# Input.net
KiCad netlist of a schematic drawn in Altium Designer
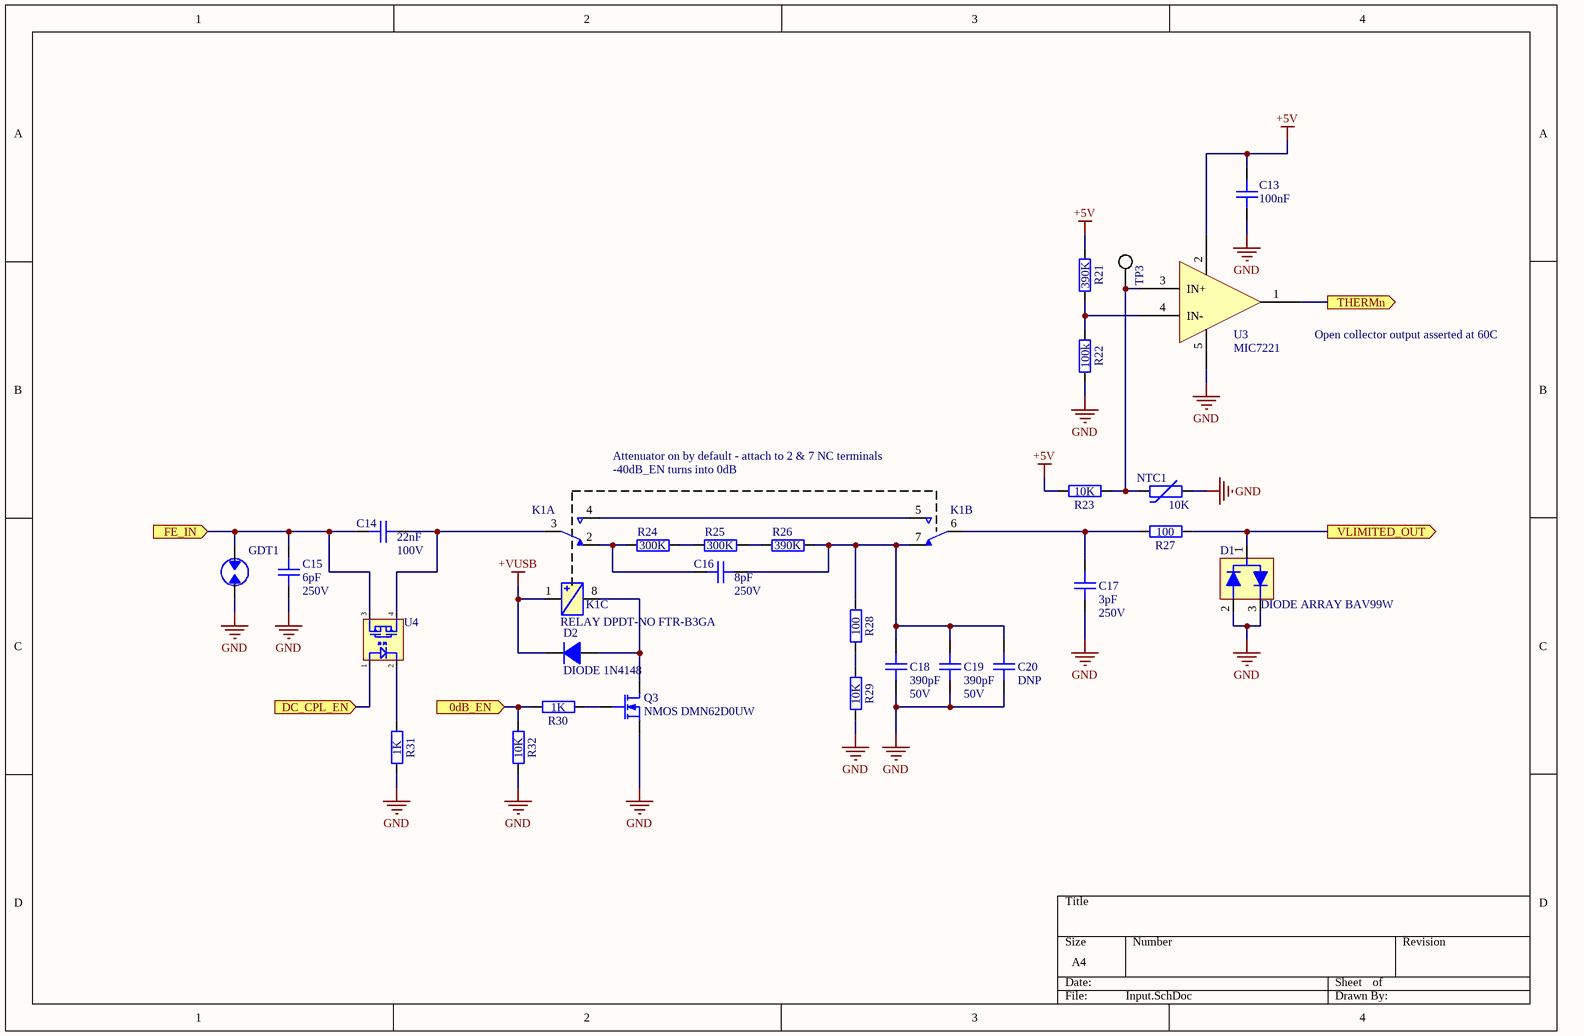
[diagram p0: Input.SchDoc]

(export (version "E")
  (design (tool "Eeschema 10.0.6"))
  (components
    (comp (ref "C13")
      (value "100nF")
      (footprint "GEN_C_0402")
      (fields (field (name "Comment") "CAP 100nF 16V X7R 0402"))
      (libsource (lib "DSO") (part "CAP 100nF 16V X7R 0402"))
    )
    (comp (ref "C14")
      (value "22nF")
      (footprint "GEN_C_0603")
      (fields (field (name "VOLTAGE RATING") "100V") (field (name "Comment") "CAP 22nF 100V X7R 0603"))
      (libsource (lib "DSO") (part "CAP 22nF 100V X7R 0603"))
    )
    (comp (ref "C15")
      (value "6pF")
      (footprint "GEN_C_0603")
      (fields (field (name "VOLTAGE RATING") "250V") (field (name "Comment") "CAP 6pF 250V C0G 0603"))
      (libsource (lib "DSO") (part "CAP 6pF 250V C0G 0603"))
    )
    (comp (ref "C16")
      (value "8pF")
      (footprint "GEN_C_0603")
      (fields (field (name "VOLTAGE RATING") "250V") (field (name "Comment") "CAP 8pF 250V C0G 0603"))
      (libsource (lib "DSO") (part "CAP 8pF 250V C0G 0603"))
    )
    (comp (ref "C17")
      (value "3pF")
      (footprint "GEN_C_0603")
      (fields (field (name "VOLTAGE RATING") "250V") (field (name "Comment") "CAP 3pF 250V C0G 0603"))
      (libsource (lib "DSO") (part "CAP 3pF 250V C0G 0603"))
    )
    (comp (ref "C18")
      (value "390pF")
      (footprint "GEN_C_0402")
      (fields (field (name "VOLTAGE RATING") "50V") (field (name "Comment") "CAP 390pF 50V C0G 0402"))
      (libsource (lib "DSO") (part "CAP 390pF 50V C0G 0402"))
    )
    (comp (ref "C19")
      (value "390pF")
      (footprint "GEN_C_0402")
      (fields (field (name "VOLTAGE RATING") "50V") (field (name "Comment") "CAP 390pF 50V C0G 0402"))
      (libsource (lib "DSO") (part "CAP 390pF 50V C0G 0402"))
    )
    (comp (ref "C20")
      (value "DNP")
      (footprint "GEN_C_0402")
      (fields (field (name "Comment") "CAP DNP 0402"))
      (libsource (lib "DSO") (part "CAP DNP 0402"))
    )
    (comp (ref "D1")
      (value "DIODE ARRAY BAV99W")
      (footprint "GEN_SOT_323")
      (libsource (lib "DSO") (part "DIODE ARRAY BAV99W"))
    )
    (comp (ref "D2")
      (value "DIODE 1N4148")
      (footprint "GEN_SOD_323")
      (libsource (lib "DSO") (part "DIODE 1N4148"))
    )
    (comp (ref "GDT1") (value "GDT 90V") (footprint "BOU_2051") (libsource (lib "DSO") (part "GDT 90V")))
    (comp (ref "K1")
      (value "RELAY DPDT-NO FTR-B3GA")
      (footprint "FUJ_FTR-B3GA")
      (libsource (lib "") (part "RELAY DPDT-NO FTR-B3GA_1"))
    )
    (comp (ref "NTC1")
      (value "10K")
      (footprint "GEN_R_0402")
      (fields (field (name "Comment") "NTC 10K 3900K 0402"))
      (libsource (lib "DSO") (part "NTC 10K 3900K 0402"))
    )
    (comp (ref "Q3")
      (value "NMOS DMN62D0UW")
      (footprint "GEN_SOT_323")
      (libsource (lib "DSO") (part "NMOS DMN62D0UW"))
    )
    (comp (ref "R21")
      (value "390K")
      (footprint "GEN_R_0402")
      (fields (field (name "TOLERANCE") "1%") (field (name "Comment") "RES 390K OHM 1% 1/10W 0402"))
      (libsource (lib "") (part "RES 390K OHM 1% 1/10W 0402_1"))
    )
    (comp (ref "R22")
      (value "100k")
      (footprint "GEN_R_0402")
      (fields (field (name "TOLERANCE") "1%") (field (name "Comment") "RES 100K OHM 1% 1/10W 0402"))
      (libsource (lib "DSO") (part "RES 100K OHM 1% 1/10W 0402"))
    )
    (comp (ref "R23")
      (value "10K")
      (footprint "GEN_R_0402")
      (fields (field (name "TOLERANCE") "1%") (field (name "Comment") "RES 10K OHM 1% 1/10W 0402"))
      (libsource (lib "") (part "RES 10K OHM 1% 1/10W 0402_1"))
    )
    (comp (ref "R24")
      (value "300K")
      (footprint "GEN_R_0402")
      (fields (field (name "TOLERANCE") "1%") (field (name "Comment") "RES 300K OHM 1% 1/10W 0402"))
      (libsource (lib "DSO") (part "RES 300K OHM 1% 1/10W 0402"))
    )
    (comp (ref "R25")
      (value "300K")
      (footprint "GEN_R_0402")
      (fields (field (name "TOLERANCE") "1%") (field (name "Comment") "RES 300K OHM 1% 1/10W 0402"))
      (libsource (lib "DSO") (part "RES 300K OHM 1% 1/10W 0402"))
    )
    (comp (ref "R26")
      (value "390K")
      (footprint "GEN_R_0402")
      (fields (field (name "TOLERANCE") "1%") (field (name "Comment") "RES 390K OHM 1% 1/10W 0402"))
      (libsource (lib "DSO") (part "RES 390K OHM 1% 1/10W 0402"))
    )
    (comp (ref "R27")
      (value "100")
      (footprint "GEN_R_0402")
      (fields (field (name "TOLERANCE") "1%") (field (name "Comment") "RES 100 OHM 1% 1/10W 0402"))
      (libsource (lib "DSO") (part "RES 100 OHM 1% 1/10W 0402"))
    )
    (comp (ref "R28")
      (value "100")
      (footprint "GEN_R_0402")
      (fields (field (name "TOLERANCE") "1%") (field (name "Comment") "RES 100 OHM 1% 1/10W 0402"))
      (libsource (lib "") (part "RES 100 OHM 1% 1/10W 0402_1"))
    )
    (comp (ref "R29")
      (value "10K")
      (footprint "GEN_R_0402")
      (fields (field (name "TOLERANCE") "1%") (field (name "Comment") "RES 10K OHM 1% 1/10W 0402"))
      (libsource (lib "DSO") (part "RES 10K OHM 1% 1/10W 0402"))
    )
    (comp (ref "R30")
      (value "1K")
      (footprint "GEN_R_0402")
      (fields (field (name "TOLERANCE") "1%") (field (name "Comment") "RES 1K OHM 1% 1/10W 0402"))
      (libsource (lib "") (part "RES 1K OHM 1% 1/10W 0402_1"))
    )
    (comp (ref "R31")
      (value "1K")
      (footprint "GEN_R_0402")
      (fields (field (name "TOLERANCE") "1%") (field (name "Comment") "RES 1K OHM 1% 1/10W 0402"))
      (libsource (lib "DSO") (part "RES 1K OHM 1% 1/10W 0402"))
    )
    (comp (ref "R32")
      (value "10K")
      (footprint "GEN_R_0402")
      (fields (field (name "TOLERANCE") "1%") (field (name "Comment") "RES 10K OHM 1% 1/10W 0402"))
      (libsource (lib "DSO") (part "RES 10K OHM 1% 1/10W 0402"))
    )
    (comp (ref "TP3") (value "5019") (footprint "KEY_5019") (libsource (lib "DSO") (part "TP KEYSTONE 5019")))
    (comp (ref "U3")
      (value "MIC7221")
      (footprint "GEN_SOT23_5_950_2900X1600X1450")
      (libsource (lib "DSO") (part "IC COMP MIC7221YM5"))
    )
    (comp (ref "U4")
      (value "SSR CPC1017NTR")
      (footprint "IXY_CPC1017")
      (libsource (lib "DSO") (part "SSR CPC1017NTR"))
    )
  )
  (nets
    (net (code "1") (name "+5V") (class "Default")
      (node (ref "C13") (pin "1") (pinfunction "1_1") (pintype "passive"))
      (node (ref "R21") (pin "1") (pinfunction "1_1") (pintype "passive"))
      (node (ref "R23") (pin "2") (pinfunction "2_2") (pintype "passive"))
      (node (ref "U3") (pin "2") (pinfunction "V+_2") (pintype "passive"))
    )
    (net (code "2") (name "+VUSB") (class "Default")
      (node (ref "D2") (pin "1") (pinfunction "K_1") (pintype "passive"))
      (node (ref "K1") (pin "1") (pinfunction "1_1") (pintype "passive"))
    )
    (net (code "3") (name "/0dB_EN") (class "Default")
      (node (ref "R30") (pin "2") (pinfunction "2_2") (pintype "passive"))
      (node (ref "R32") (pin "2") (pinfunction "2_2") (pintype "passive"))
    )
    (net (code "4") (name "/DC_CPL_EN") (class "Default")
      (node (ref "U4") (pin "1") (pinfunction "1_1") (pintype "passive"))
    )
    (net (code "5") (name "/FE_IN") (class "Default")
      (node (ref "C14") (pin "2") (pinfunction "2_2") (pintype "passive"))
      (node (ref "C15") (pin "2") (pinfunction "2_2") (pintype "passive"))
      (node (ref "GDT1") (pin "1") (pinfunction "1_1") (pintype "passive"))
      (node (ref "U4") (pin "3") (pinfunction "3_3") (pintype "passive"))
    )
    (net (code "6") (name "/THERMn") (class "Default")
      (node (ref "U3") (pin "1") (pinfunction "OUT_1") (pintype "open_collector"))
    )
    (net (code "7") (name "/VLIMITED_OUT") (class "Default")
      (node (ref "D1") (pin "1") (pintype "passive"))
      (node (ref "R27") (pin "1") (pinfunction "1_1") (pintype "passive"))
    )
    (net (code "8") (name "GND") (class "Default")
      (node (ref "C13") (pin "2") (pinfunction "2_2") (pintype "passive"))
      (node (ref "C15") (pin "1") (pinfunction "1_1") (pintype "passive"))
      (node (ref "C17") (pin "2") (pinfunction "2_2") (pintype "passive"))
      (node (ref "C18") (pin "1") (pinfunction "1_1") (pintype "passive"))
      (node (ref "C19") (pin "1") (pinfunction "1_1") (pintype "passive"))
      (node (ref "C20") (pin "1") (pinfunction "1_1") (pintype "passive"))
      (node (ref "D1") (pin "2") (pinfunction "2_2") (pintype "passive"))
      (node (ref "D1") (pin "3") (pinfunction "3_3") (pintype "passive"))
      (node (ref "GDT1") (pin "2") (pinfunction "2_2") (pintype "passive"))
      (node (ref "NTC1") (pin "2") (pinfunction "2_2") (pintype "passive"))
      (node (ref "Q3") (pin "3") (pinfunction "S_3") (pintype "passive"))
      (node (ref "R22") (pin "2") (pinfunction "2_2") (pintype "passive"))
      (node (ref "R29") (pin "1") (pinfunction "1_1") (pintype "passive"))
      (node (ref "R31") (pin "1") (pinfunction "1_1") (pintype "passive"))
      (node (ref "R32") (pin "1") (pinfunction "1_1") (pintype "passive"))
      (node (ref "U3") (pin "5") (pinfunction "V-_5") (pintype "passive"))
    )
    (net (code "9") (name "Net-(C14-Pad1)") (class "Default")
      (node (ref "C14") (pin "1") (pinfunction "1_1") (pintype "passive"))
      (node (ref "K1") (pin "3") (pinfunction "3_3") (pintype "passive"))
      (node (ref "U4") (pin "4") (pinfunction "4_4") (pintype "passive"))
    )
    (net (code "10") (name "Net-(C16-Pad1)") (class "Default")
      (node (ref "C16") (pin "1") (pinfunction "1_1") (pintype "passive"))
      (node (ref "C18") (pin "2") (pinfunction "2_2") (pintype "passive"))
      (node (ref "C19") (pin "2") (pinfunction "2_2") (pintype "passive"))
      (node (ref "C20") (pin "2") (pinfunction "2_2") (pintype "passive"))
      (node (ref "K1") (pin "7") (pinfunction "7_7") (pintype "passive"))
      (node (ref "R26") (pin "2") (pinfunction "2_2") (pintype "passive"))
      (node (ref "R28") (pin "2") (pinfunction "2_2") (pintype "passive"))
    )
    (net (code "11") (name "Net-(C16-Pad2)") (class "Default")
      (node (ref "C16") (pin "2") (pinfunction "2_2") (pintype "passive"))
      (node (ref "K1") (pin "2") (pinfunction "2_2") (pintype "passive"))
      (node (ref "R24") (pin "1") (pinfunction "1_1") (pintype "passive"))
    )
    (net (code "12") (name "Net-(C17-Pad1)") (class "Default")
      (node (ref "C17") (pin "1") (pinfunction "1_1") (pintype "passive"))
      (node (ref "K1") (pin "6") (pinfunction "6_6") (pintype "passive"))
      (node (ref "R27") (pin "2") (pinfunction "2_2") (pintype "passive"))
    )
    (net (code "13") (name "Net-(D2-A)") (class "Default")
      (node (ref "D2") (pin "2") (pinfunction "A_2") (pintype "passive"))
      (node (ref "K1") (pin "8") (pinfunction "8_8") (pintype "passive"))
      (node (ref "Q3") (pin "1") (pinfunction "D_1") (pintype "passive"))
    )
    (net (code "14") (name "Net-(K1-Pad4)") (class "Default")
      (node (ref "K1") (pin "4") (pinfunction "4_4") (pintype "passive"))
      (node (ref "K1") (pin "5") (pinfunction "5_5") (pintype "passive"))
    )
    (net (code "15") (name "Net-(Q3-G)") (class "Default")
      (node (ref "Q3") (pin "2") (pinfunction "G_2") (pintype "passive"))
      (node (ref "R30") (pin "1") (pinfunction "1_1") (pintype "passive"))
    )
    (net (code "16") (name "Net-(R24-Pad2)") (class "Default")
      (node (ref "R24") (pin "2") (pinfunction "2_2") (pintype "passive"))
      (node (ref "R25") (pin "1") (pinfunction "1_1") (pintype "passive"))
    )
    (net (code "17") (name "Net-(R25-Pad2)") (class "Default")
      (node (ref "R25") (pin "2") (pinfunction "2_2") (pintype "passive"))
      (node (ref "R26") (pin "1") (pinfunction "1_1") (pintype "passive"))
    )
    (net (code "18") (name "Net-(R28-Pad1)") (class "Default")
      (node (ref "R28") (pin "1") (pinfunction "1_1") (pintype "passive"))
      (node (ref "R29") (pin "2") (pinfunction "2_2") (pintype "passive"))
    )
    (net (code "19") (name "Net-(R31-Pad2)") (class "Default")
      (node (ref "R31") (pin "2") (pinfunction "2_2") (pintype "passive"))
      (node (ref "U4") (pin "2") (pinfunction "2_2") (pintype "passive"))
    )
    (net (code "20") (name "Net-(U3-IN+)") (class "Default")
      (node (ref "NTC1") (pin "1") (pinfunction "1_1") (pintype "passive"))
      (node (ref "R23") (pin "1") (pinfunction "1_1") (pintype "passive"))
      (node (ref "TP3") (pin "1") (pinfunction "1_1") (pintype "passive"))
      (node (ref "U3") (pin "3") (pinfunction "IN+_3") (pintype "passive"))
    )
    (net (code "21") (name "Net-(U3-IN-)") (class "Default")
      (node (ref "R21") (pin "2") (pinfunction "2_2") (pintype "passive"))
      (node (ref "R22") (pin "1") (pinfunction "1_1") (pintype "passive"))
      (node (ref "U3") (pin "4") (pinfunction "IN-_4") (pintype "passive"))
    )
  )
)
